# MOD-v2-1_MOD-Strips.net
KiCad netlist of a schematic drawn in EAGLE
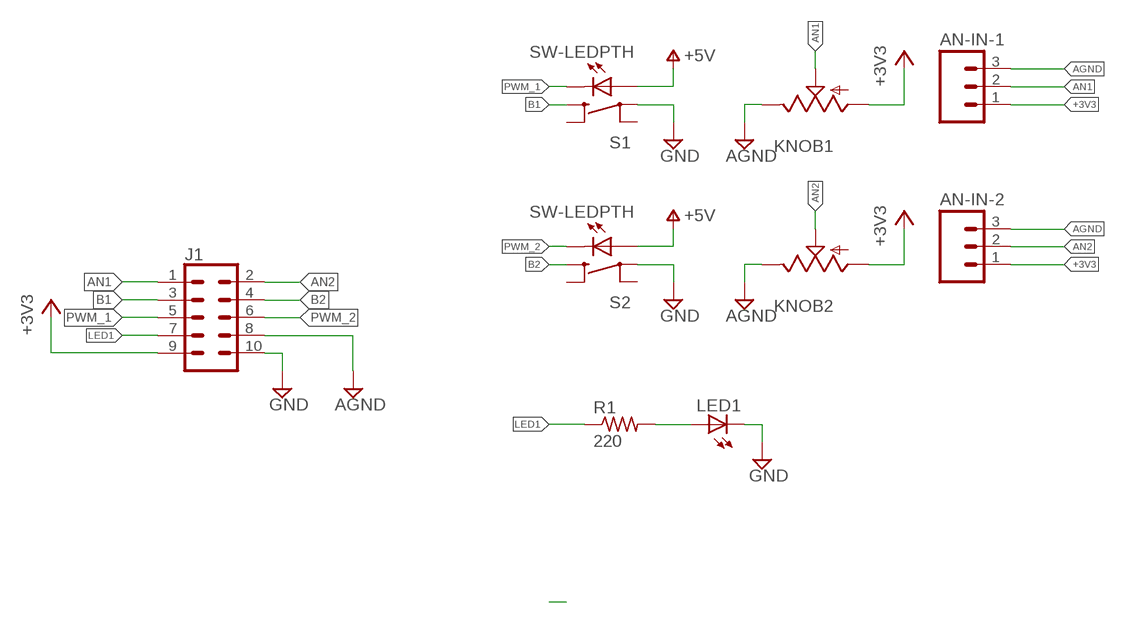
[diagram p0: schematic, sheet 1]

(export (version "E")
  (design (tool "Eeschema 10.0.6"))
  (components
    (comp (ref "AN-IN-1")
      (value "M031X03_NO_SILK")
      (footprint "eagle-import:1X03_NO_SILK")
      (libsource (lib "eagle-import") (part "M031X03_NO_SILK"))
    )
    (comp (ref "AN-IN-2")
      (value "M031X03_NO_SILK")
      (footprint "eagle-import:1X03_NO_SILK")
      (libsource (lib "eagle-import") (part "M031X03_NO_SILK"))
    )
    (comp (ref "J1")
      (value "CONN_05X2SHD_LOCK")
      (footprint "eagle-import:2X5-SHROUDED_LOCK")
      (libsource (lib "eagle-import") (part "CONN_05X2SHD_LOCK"))
    )
    (comp (ref "KNOB1")
      (value "TRIM")
      (footprint "eagle-import:TRIM-PCB-9MM")
      (libsource (lib "eagle-import") (part "TRIM"))
    )
    (comp (ref "KNOB2")
      (value "TRIM")
      (footprint "eagle-import:TRIM-PCB-9MM")
      (libsource (lib "eagle-import") (part "TRIM"))
    )
    (comp (ref "LED1")
      (value "LED3MM")
      (footprint "eagle-import:LED3MM")
      (libsource (lib "eagle-import") (part "LED3MM"))
    )
    (comp (ref "R1")
      (value "220")
      (footprint "eagle-import:0204_7")
      (libsource (lib "eagle-import") (part "R-US_0204/7"))
    )
    (comp (ref "S1")
      (value "SW-LEDPTH")
      (footprint "eagle-import:TR2-SWITCH-MOMENTARY-LED")
      (libsource (lib "eagle-import") (part "SW-LEDPTH"))
    )
    (comp (ref "S2")
      (value "SW-LEDPTH")
      (footprint "eagle-import:TR2-SWITCH-MOMENTARY-LED")
      (libsource (lib "eagle-import") (part "SW-LEDPTH"))
    )
  )
  (nets
    (net (code "1") (name "+3V3") (class "Default")
      (node (ref "AN-IN-1") (pin "1") (pinfunction "1_1") (pintype "passive"))
      (node (ref "AN-IN-2") (pin "1") (pinfunction "1_1") (pintype "passive"))
      (node (ref "J1") (pin "9") (pinfunction "9_9") (pintype "passive"))
      (node (ref "KNOB1") (pin "1") (pinfunction "A_1") (pintype "passive"))
      (node (ref "KNOB2") (pin "1") (pinfunction "A_1") (pintype "passive"))
    )
    (net (code "2") (name "AGND") (class "Default")
      (node (ref "AN-IN-1") (pin "3") (pinfunction "3_3") (pintype "passive"))
      (node (ref "AN-IN-2") (pin "3") (pinfunction "3_3") (pintype "passive"))
      (node (ref "J1") (pin "8") (pinfunction "8_8") (pintype "passive"))
      (node (ref "KNOB1") (pin "3") (pinfunction "E_3") (pintype "passive"))
      (node (ref "KNOB2") (pin "3") (pinfunction "E_3") (pintype "passive"))
    )
    (net (code "3") (name "AN1") (class "Default")
      (node (ref "AN-IN-1") (pin "2") (pinfunction "2_2") (pintype "passive"))
      (node (ref "J1") (pin "1") (pinfunction "1_1") (pintype "passive"))
      (node (ref "KNOB1") (pin "2") (pinfunction "S_2") (pintype "passive"))
    )
    (net (code "4") (name "AN2") (class "Default")
      (node (ref "AN-IN-2") (pin "2") (pinfunction "2_2") (pintype "passive"))
      (node (ref "J1") (pin "2") (pinfunction "2_2") (pintype "passive"))
      (node (ref "KNOB2") (pin "2") (pinfunction "S_2") (pintype "passive"))
    )
    (net (code "5") (name "B1") (class "Default")
      (node (ref "J1") (pin "3") (pinfunction "3_3") (pintype "passive"))
      (node (ref "S1") (pin "1") (pinfunction "1_1") (pintype "passive"))
    )
    (net (code "6") (name "B2") (class "Default")
      (node (ref "J1") (pin "4") (pinfunction "4_4") (pintype "passive"))
      (node (ref "S2") (pin "1") (pinfunction "1_1") (pintype "passive"))
    )
    (net (code "7") (name "GND") (class "Default")
      (node (ref "J1") (pin "10") (pinfunction "10_10") (pintype "passive"))
      (node (ref "LED1") (pin "K") (pinfunction "C_K") (pintype "passive"))
      (node (ref "S1") (pin "3") (pinfunction "3_3") (pintype "passive"))
      (node (ref "S2") (pin "3") (pinfunction "3_3") (pintype "passive"))
    )
    (net (code "8") (name "LED1") (class "Default")
      (node (ref "J1") (pin "7") (pinfunction "7_7") (pintype "passive"))
      (node (ref "R1") (pin "1") (pinfunction "1_1") (pintype "passive"))
    )
    (net (code "9") (name "Net-(LED1-PadA)") (class "Default")
      (node (ref "LED1") (pin "A") (pinfunction "A_A") (pintype "passive"))
      (node (ref "R1") (pin "2") (pinfunction "2_2") (pintype "passive"))
    )
    (net (code "10") (name "PWM_1") (class "Default")
      (node (ref "J1") (pin "5") (pinfunction "5_5") (pintype "passive"))
      (node (ref "S1") (pin "C") (pinfunction "C_C") (pintype "passive"))
    )
    (net (code "11") (name "PWM_2") (class "Default")
      (node (ref "J1") (pin "6") (pinfunction "6_6") (pintype "passive"))
      (node (ref "S2") (pin "C") (pinfunction "C_C") (pintype "passive"))
    )
    (net (code "12") (name "V+") (class "Default")
      (node (ref "S1") (pin "A") (pinfunction "A_A") (pintype "passive"))
      (node (ref "S2") (pin "A") (pinfunction "A_A") (pintype "passive"))
    )
    (net (code "13") (name "unconnected-(S1-Pad2)") (class "Default")
      (node (ref "S1") (pin "2") (pinfunction "2_2") (pintype "passive"))
    )
    (net (code "14") (name "unconnected-(S1-Pad4)") (class "Default")
      (node (ref "S1") (pin "4") (pinfunction "4_4") (pintype "passive"))
    )
    (net (code "15") (name "unconnected-(S2-Pad2)") (class "Default")
      (node (ref "S2") (pin "2") (pinfunction "2_2") (pintype "passive"))
    )
    (net (code "16") (name "unconnected-(S2-Pad4)") (class "Default")
      (node (ref "S2") (pin "4") (pinfunction "4_4") (pintype "passive"))
    )
  )
)
